# LCD_Header.net
KiCad netlist of a schematic drawn in Altium Designer
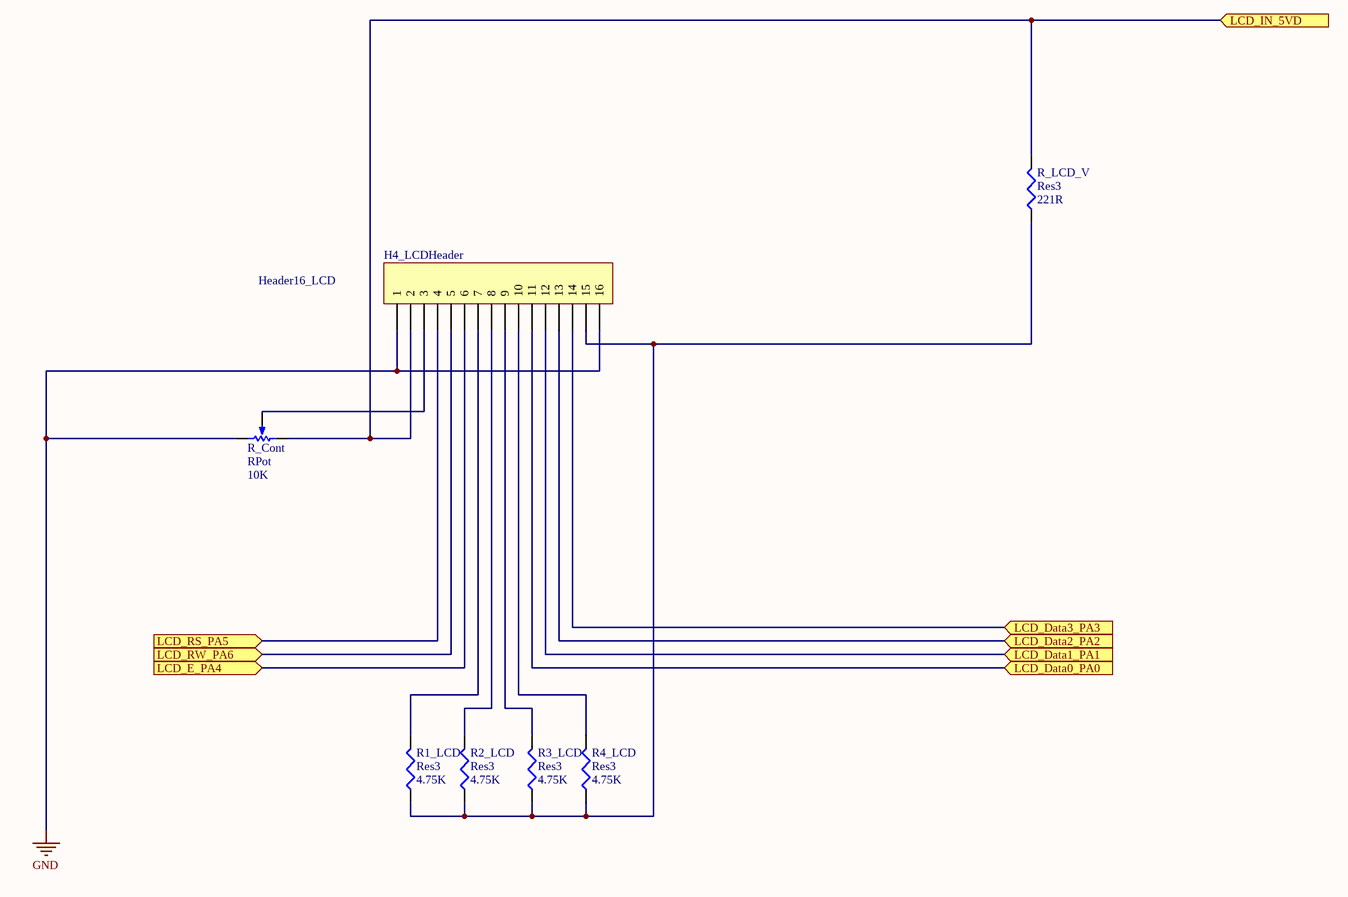
[diagram p0: LCD_Header.SchDoc]

(export (version "E")
  (design (tool "Eeschema 10.0.6"))
  (components
    (comp (ref "H4_LCDHeader")
      (value "Header16_LCD")
      (footprint "HDR1X16_LCD")
      (description "Header, 16-Pin Female")
      (fields (field (name "MPN") "PPPC161LFBN-RC"))
      (libsource (lib "esd_library") (part "Header16_LCD"))
    )
    (comp (ref "R1_LCD")
      (value "Res3")
      (footprint "RESC2112X05M")
      (description "RES SMD 4.75K OHM 1% 1/8W 0805")
      (fields (field (name "ALTIUM_VALUE") "4.75K") (field (name "MPN") "CRCW08054K75FKEA"))
      (libsource (lib "esd_library") (part "Resistor_4.75K"))
    )
    (comp (ref "R2_LCD")
      (value "Res3")
      (footprint "RESC2112X05M")
      (description "RES SMD 4.75K OHM 1% 1/8W 0805")
      (fields (field (name "ALTIUM_VALUE") "4.75K") (field (name "MPN") "CRCW08054K75FKEA"))
      (libsource (lib "esd_library") (part "Resistor_4.75K"))
    )
    (comp (ref "R3_LCD")
      (value "Res3")
      (footprint "RESC2112X05M")
      (description "RES SMD 4.75K OHM 1% 1/8W 0805")
      (fields (field (name "ALTIUM_VALUE") "4.75K") (field (name "MPN") "CRCW08054K75FKEA"))
      (libsource (lib "esd_library") (part "Resistor_4.75K"))
    )
    (comp (ref "R4_LCD")
      (value "Res3")
      (footprint "RESC2112X05M")
      (description "RES SMD 4.75K OHM 1% 1/8W 0805")
      (fields (field (name "ALTIUM_VALUE") "4.75K") (field (name "MPN") "CRCW08054K75FKEA"))
      (libsource (lib "esd_library") (part "Resistor_4.75K"))
    )
    (comp (ref "R_Cont")
      (value "RPot")
      (footprint "BOURNS_3386F")
      (description "Potentiometer")
      (fields (field (name "ALTIUM_VALUE") "10K") (field (name "PUBLISHER") "Altium Limited"))
      (libsource (lib "esd_library") (part "RPot"))
    )
    (comp (ref "R_LCD_V")
      (value "Res3")
      (footprint "RESC2112X05M")
      (description "RES SMD 221R OHM 1% 1/8W 0805")
      (fields (field (name "ALTIUM_VALUE") "221R") (field (name "MPN") "CRCW0805221RFKEA"))
      (libsource (lib "esd_library") (part "Resistor_221R"))
    )
  )
  (nets
    (net (code "1") (name "/LCD_Data0_PA0") (class "Default")
      (node (ref "H4_LCDHeader") (pin "11") (pinfunction "11_11") (pintype "passive"))
    )
    (net (code "2") (name "/LCD_Data1_PA1") (class "Default")
      (node (ref "H4_LCDHeader") (pin "12") (pinfunction "12_12") (pintype "passive"))
    )
    (net (code "3") (name "/LCD_Data2_PA2") (class "Default")
      (node (ref "H4_LCDHeader") (pin "13") (pinfunction "13_13") (pintype "passive"))
    )
    (net (code "4") (name "/LCD_Data3_PA3") (class "Default")
      (node (ref "H4_LCDHeader") (pin "14") (pinfunction "14_14") (pintype "passive"))
    )
    (net (code "5") (name "/LCD_E_PA4") (class "Default")
      (node (ref "H4_LCDHeader") (pin "6") (pinfunction "6_6") (pintype "passive"))
    )
    (net (code "6") (name "/LCD_IN_5VD") (class "Default")
      (node (ref "H4_LCDHeader") (pin "2") (pinfunction "2_2") (pintype "passive"))
      (node (ref "R_Cont") (pin "1") (pinfunction "TOP_1") (pintype "passive"))
      (node (ref "R_LCD_V") (pin "2") (pinfunction "2_2") (pintype "passive"))
    )
    (net (code "7") (name "/LCD_RS_PA5") (class "Default")
      (node (ref "H4_LCDHeader") (pin "4") (pinfunction "4_4") (pintype "passive"))
    )
    (net (code "8") (name "/LCD_RW_PA6") (class "Default")
      (node (ref "H4_LCDHeader") (pin "5") (pinfunction "5_5") (pintype "passive"))
    )
    (net (code "9") (name "GND") (class "Default")
      (node (ref "H4_LCDHeader") (pin "1") (pinfunction "1_1") (pintype "passive"))
      (node (ref "H4_LCDHeader") (pin "16") (pinfunction "16_16") (pintype "passive"))
      (node (ref "R_Cont") (pin "3") (pinfunction "BOT_3") (pintype "passive"))
    )
    (net (code "10") (name "Net-(H4_LCDHeader-Pad7)") (class "Default")
      (node (ref "H4_LCDHeader") (pin "7") (pinfunction "7_7") (pintype "passive"))
      (node (ref "R1_LCD") (pin "2") (pinfunction "2_2") (pintype "passive"))
    )
    (net (code "11") (name "Net-(H4_LCDHeader-Pad8)") (class "Default")
      (node (ref "H4_LCDHeader") (pin "8") (pinfunction "8_8") (pintype "passive"))
      (node (ref "R2_LCD") (pin "2") (pinfunction "2_2") (pintype "passive"))
    )
    (net (code "12") (name "Net-(H4_LCDHeader-Pad9)") (class "Default")
      (node (ref "H4_LCDHeader") (pin "9") (pinfunction "9_9") (pintype "passive"))
      (node (ref "R3_LCD") (pin "2") (pinfunction "2_2") (pintype "passive"))
    )
    (net (code "13") (name "Net-(H4_LCDHeader-Pad10)") (class "Default")
      (node (ref "H4_LCDHeader") (pin "10") (pinfunction "10_10") (pintype "passive"))
      (node (ref "R4_LCD") (pin "2") (pinfunction "2_2") (pintype "passive"))
    )
    (net (code "14") (name "Net-(H4_LCDHeader-Pad15)") (class "Default")
      (node (ref "H4_LCDHeader") (pin "15") (pinfunction "15_15") (pintype "passive"))
      (node (ref "R1_LCD") (pin "1") (pinfunction "1_1") (pintype "passive"))
      (node (ref "R2_LCD") (pin "1") (pinfunction "1_1") (pintype "passive"))
      (node (ref "R3_LCD") (pin "1") (pinfunction "1_1") (pintype "passive"))
      (node (ref "R4_LCD") (pin "1") (pinfunction "1_1") (pintype "passive"))
      (node (ref "R_LCD_V") (pin "1") (pinfunction "1_1") (pintype "passive"))
    )
    (net (code "15") (name "Net-(R_Cont-TAP)") (class "Default")
      (node (ref "H4_LCDHeader") (pin "3") (pinfunction "3_3") (pintype "passive"))
      (node (ref "R_Cont") (pin "2") (pinfunction "TAP_2") (pintype "passive"))
    )
  )
)
